# AU_MacroPad.net
KiCad netlist of a schematic drawn in EAGLE
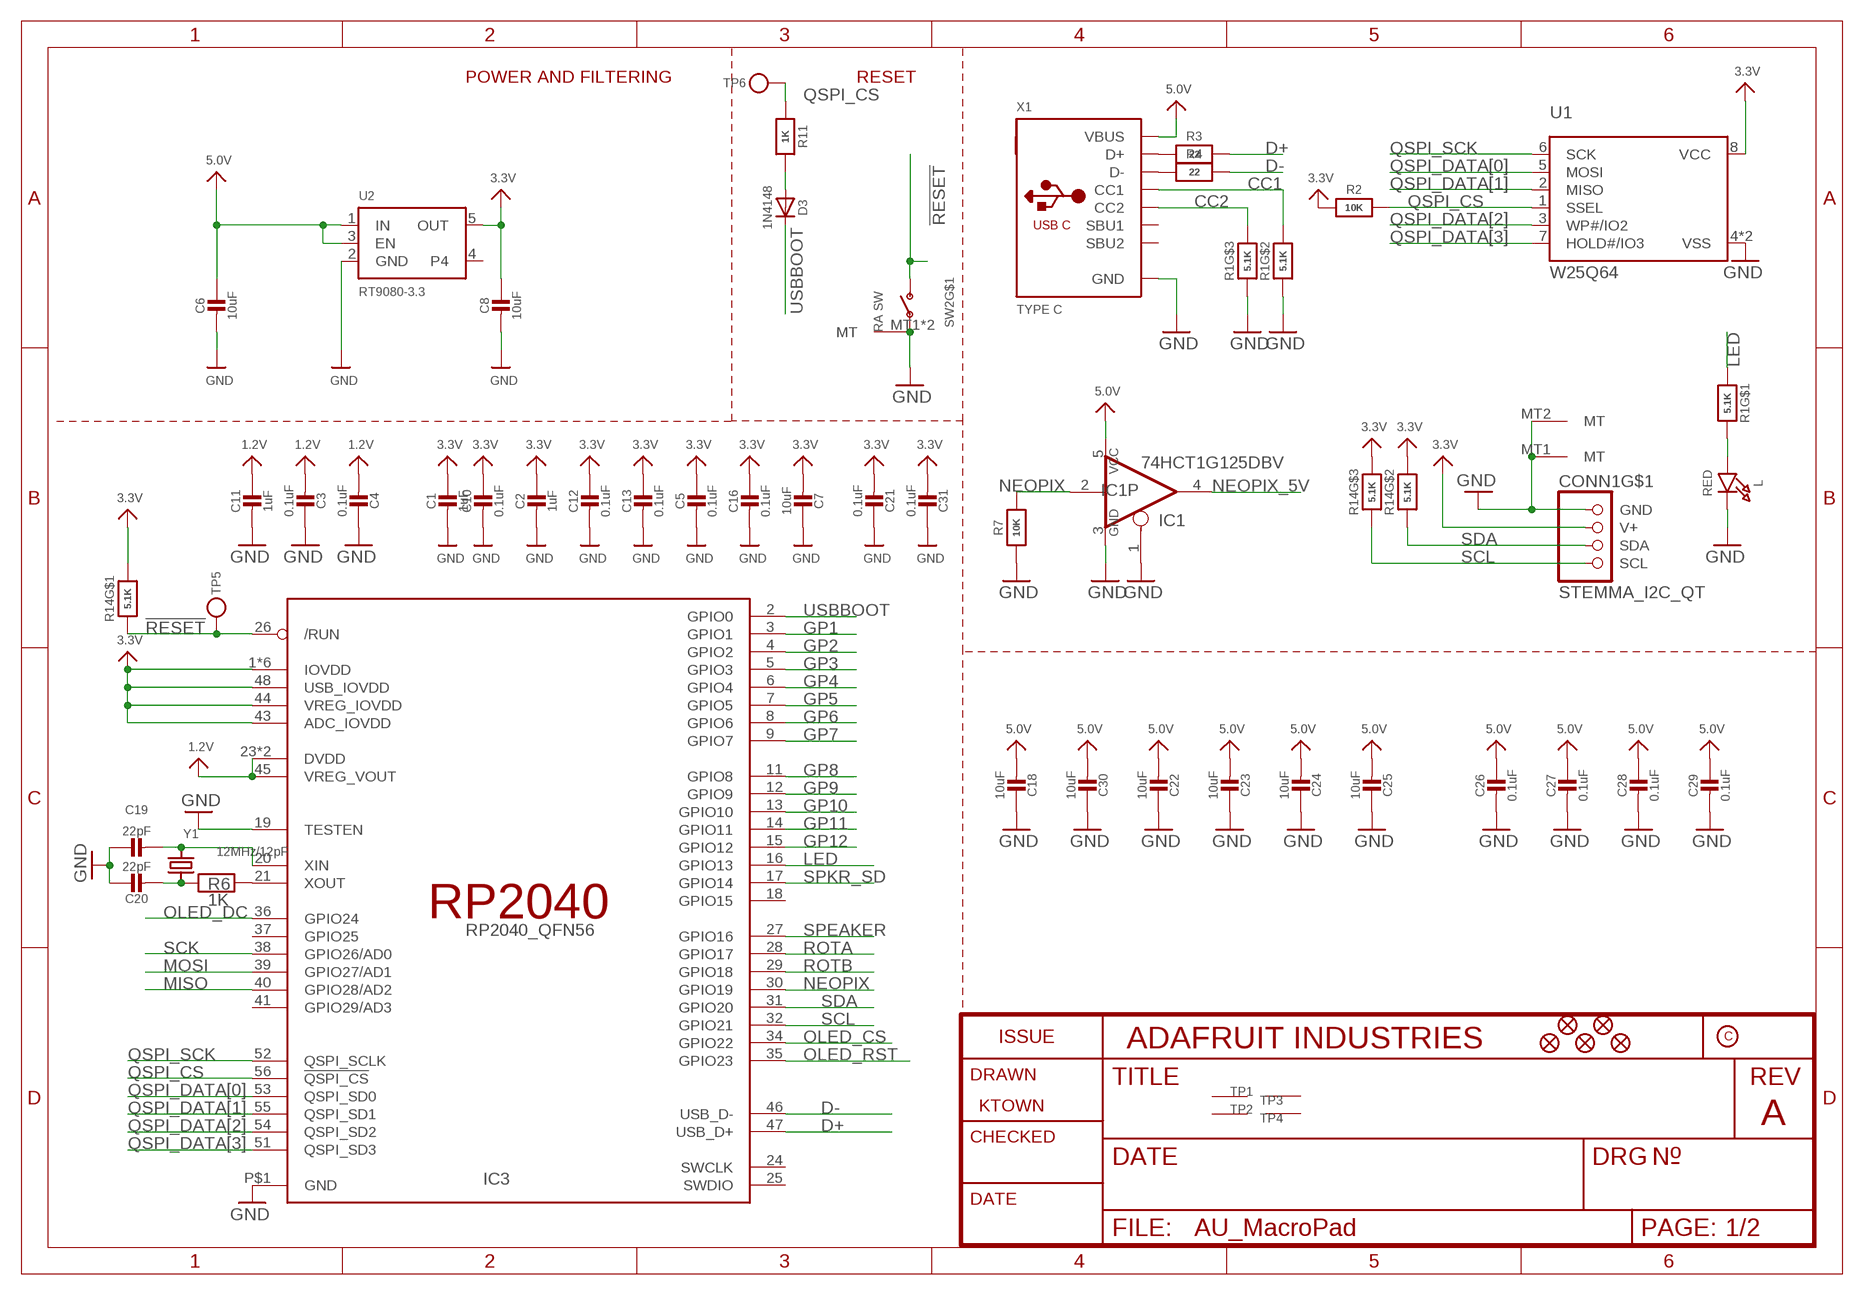
[diagram p0: schematic, sheet 1]
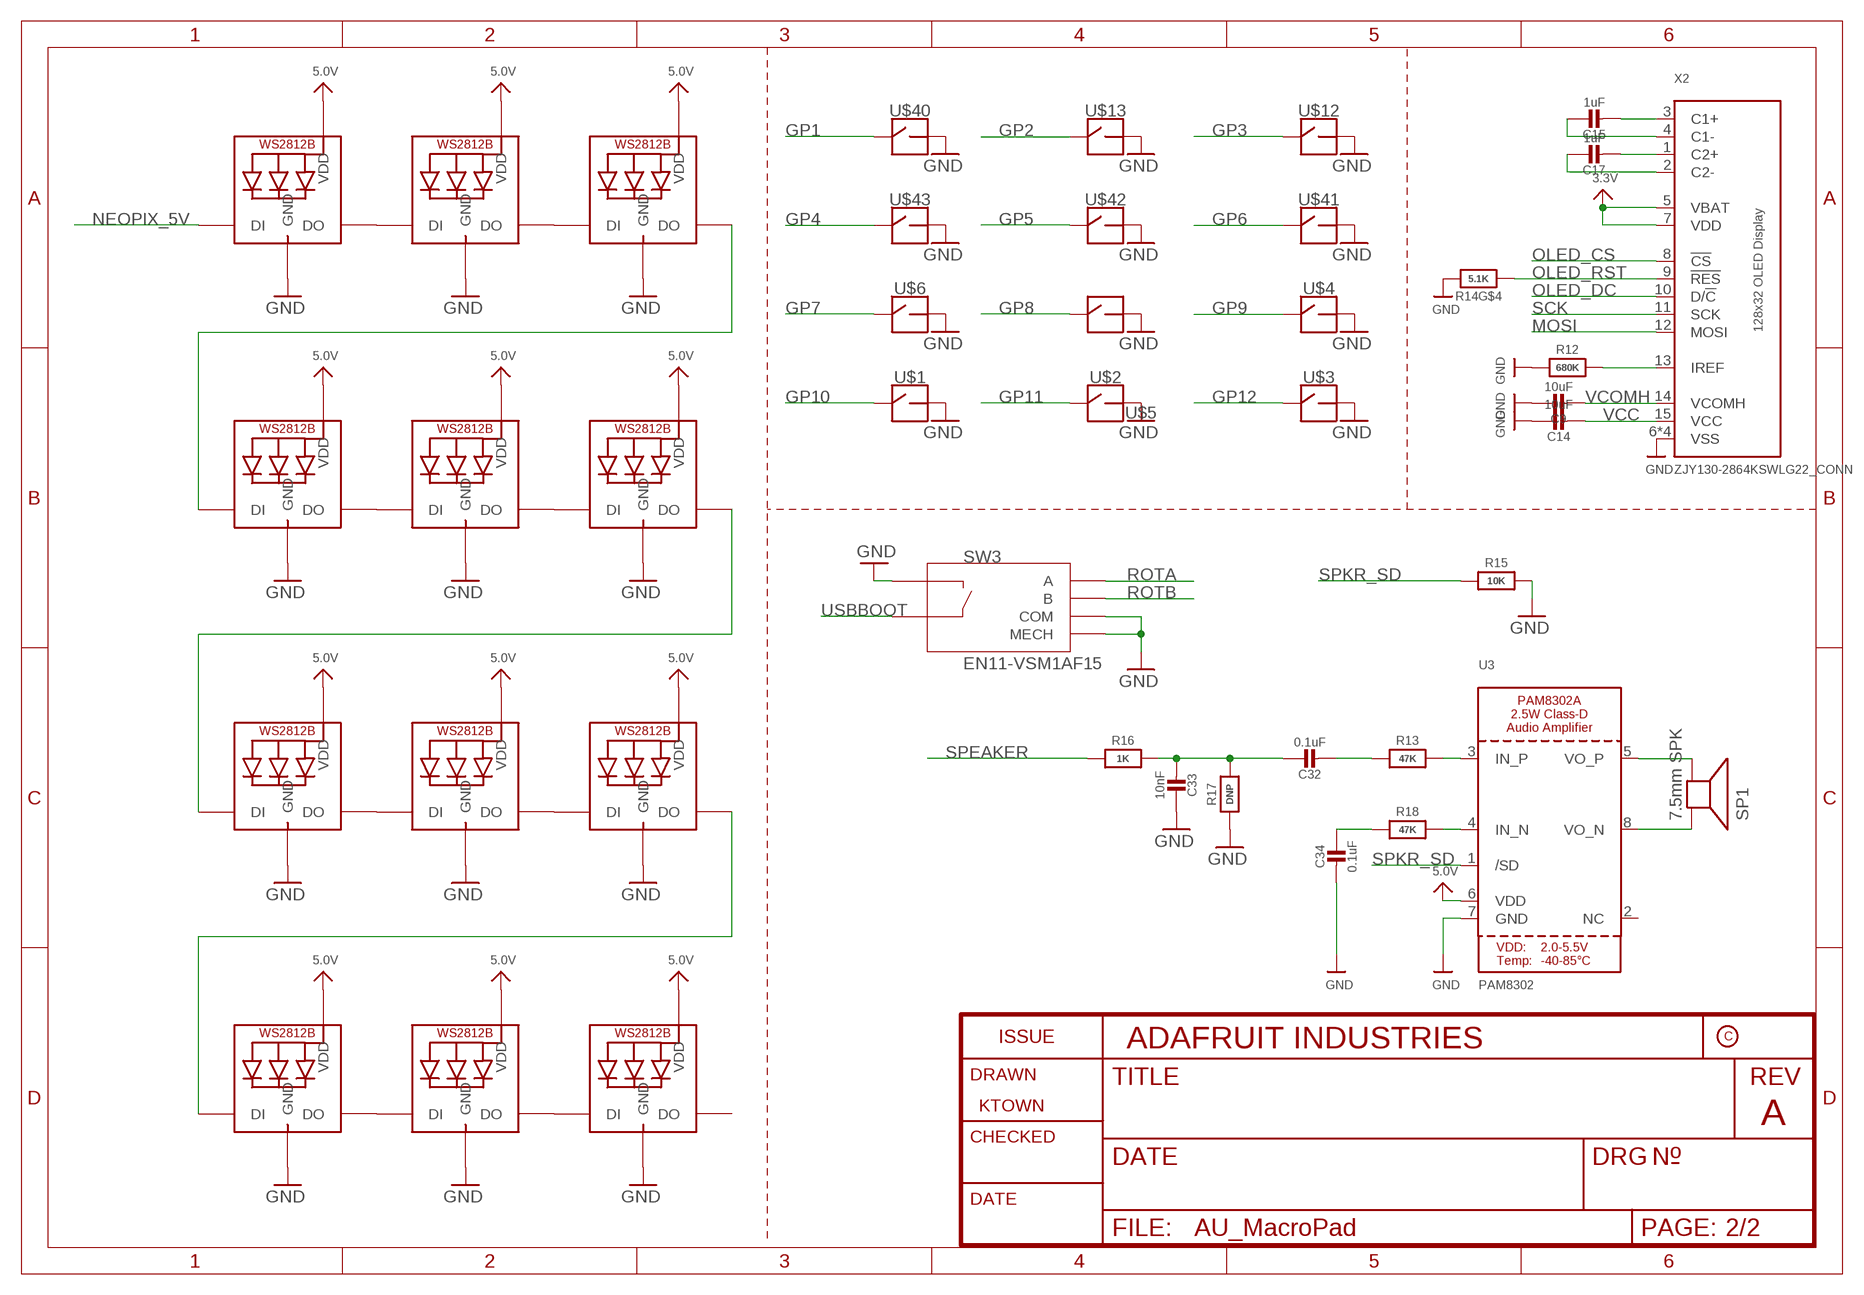
[diagram p1: schematic, sheet 2]

(export (version "E")
  (design (tool "Eeschema 10.0.6"))
  (components
    (comp (ref "C9")
      (value "10uF")
      (footprint "eagle-import:0805-NO")
      (libsource (lib "eagle-import") (part "CAP_CERAMIC0805-NOOUTLINE"))
    )
    (comp (ref "C14")
      (value "10uF")
      (footprint "eagle-import:0805-NO")
      (libsource (lib "eagle-import") (part "CAP_CERAMIC0805-NOOUTLINE"))
    )
    (comp (ref "C15")
      (value "1uF")
      (footprint "eagle-import:0603-NO")
      (libsource (lib "eagle-import") (part "CAP_CERAMIC0603_NO"))
    )
    (comp (ref "C17")
      (value "1uF")
      (footprint "eagle-import:0603-NO")
      (libsource (lib "eagle-import") (part "CAP_CERAMIC0603_NO"))
    )
    (comp (ref "C32")
      (value "0.1uF")
      (footprint "eagle-import:0603-NO")
      (libsource (lib "eagle-import") (part "CAP_CERAMIC0603_NO"))
    )
    (comp (ref "C33")
      (value "10nF")
      (footprint "eagle-import:0603-NO")
      (libsource (lib "eagle-import") (part "CAP_CERAMIC0603_NO"))
    )
    (comp (ref "C34")
      (value "0.1uF")
      (footprint "eagle-import:0603-NO")
      (libsource (lib "eagle-import") (part "CAP_CERAMIC0603_NO"))
    )
    (comp (ref "LED1")
      (value "WS2812B_SK6812E")
      (footprint "eagle-import:NEO3535_REVERSE")
      (libsource (lib "eagle-import") (part "WS2812B_SK6812E"))
    )
    (comp (ref "LED2")
      (value "WS2812B_SK6812E")
      (footprint "eagle-import:NEO3535_REVERSE")
      (libsource (lib "eagle-import") (part "WS2812B_SK6812E"))
    )
    (comp (ref "LED3")
      (value "WS2812B_SK6812E")
      (footprint "eagle-import:NEO3535_REVERSE")
      (libsource (lib "eagle-import") (part "WS2812B_SK6812E"))
    )
    (comp (ref "LED4")
      (value "WS2812B_SK6812E")
      (footprint "eagle-import:NEO3535_REVERSE")
      (libsource (lib "eagle-import") (part "WS2812B_SK6812E"))
    )
    (comp (ref "LED5")
      (value "WS2812B_SK6812E")
      (footprint "eagle-import:NEO3535_REVERSE")
      (libsource (lib "eagle-import") (part "WS2812B_SK6812E"))
    )
    (comp (ref "LED6")
      (value "WS2812B_SK6812E")
      (footprint "eagle-import:NEO3535_REVERSE")
      (libsource (lib "eagle-import") (part "WS2812B_SK6812E"))
    )
    (comp (ref "LED7")
      (value "WS2812B_SK6812E")
      (footprint "eagle-import:NEO3535_REVERSE")
      (libsource (lib "eagle-import") (part "WS2812B_SK6812E"))
    )
    (comp (ref "LED8")
      (value "WS2812B_SK6812E")
      (footprint "eagle-import:NEO3535_REVERSE")
      (libsource (lib "eagle-import") (part "WS2812B_SK6812E"))
    )
    (comp (ref "LED9")
      (value "WS2812B_SK6812E")
      (footprint "eagle-import:NEO3535_REVERSE")
      (libsource (lib "eagle-import") (part "WS2812B_SK6812E"))
    )
    (comp (ref "LED10")
      (value "WS2812B_SK6812E")
      (footprint "eagle-import:NEO3535_REVERSE")
      (libsource (lib "eagle-import") (part "WS2812B_SK6812E"))
    )
    (comp (ref "LED11")
      (value "WS2812B_SK6812E")
      (footprint "eagle-import:NEO3535_REVERSE")
      (libsource (lib "eagle-import") (part "WS2812B_SK6812E"))
    )
    (comp (ref "LED12")
      (value "WS2812B_SK6812E")
      (footprint "eagle-import:NEO3535_REVERSE")
      (libsource (lib "eagle-import") (part "WS2812B_SK6812E"))
    )
    (comp (ref "R12")
      (value "680K")
      (footprint "eagle-import:0603-NO")
      (libsource (lib "eagle-import") (part "RESISTOR_0603_NOOUT"))
    )
    (comp (ref "R13")
      (value "47K")
      (footprint "eagle-import:0603-NO")
      (libsource (lib "eagle-import") (part "RESISTOR_0603_NOOUT"))
    )
    (comp (ref "R14")
      (value "5.1K")
      (footprint "eagle-import:RESPACK_4X0603")
      (libsource (lib "eagle-import") (part "RESISTOR_4PACK"))
    )
    (comp (ref "R15")
      (value "10K")
      (footprint "eagle-import:0603-NO")
      (libsource (lib "eagle-import") (part "RESISTOR_0603_NOOUT"))
    )
    (comp (ref "R16")
      (value "1K")
      (footprint "eagle-import:0603-NO")
      (libsource (lib "eagle-import") (part "RESISTOR_0603_NOOUT"))
    )
    (comp (ref "R17")
      (value "DNP")
      (footprint "eagle-import:0603-NO")
      (libsource (lib "eagle-import") (part "RESISTOR_0603_NOOUT"))
    )
    (comp (ref "R18")
      (value "47K")
      (footprint "eagle-import:0603-NO")
      (libsource (lib "eagle-import") (part "RESISTOR_0603_NOOUT"))
    )
    (comp (ref "SP1")
      (value "7.5mm SPK")
      (footprint "eagle-import:BUZZER_SMT_7.5MM")
      (fields (field (name "ROT") "0"))
      (libsource (lib "eagle-import") (part "SPEAKER_7.5MM"))
    )
    (comp (ref "SW3")
      (value "EN11-VSM1AF15")
      (footprint "eagle-import:EN11-VSM1AF15")
      (libsource (lib "eagle-import") (part "EN11-VSM1AF15"))
    )
    (comp (ref "U$1")
      (value "SOCKET")
      (footprint "eagle-import:KAILH_SOCKET")
      (fields (field (name "XOFFSET") "-0.75"))
      (libsource (lib "eagle-import") (part "KBD_SWITCH_KAILH_SOCKETBOX_JADE_KAILH_SOCKET"))
    )
    (comp (ref "U$2")
      (value "SOCKET")
      (footprint "eagle-import:KAILH_SOCKET")
      (fields (field (name "XOFFSET") "-0.75"))
      (libsource (lib "eagle-import") (part "KBD_SWITCH_KAILH_SOCKETBOX_JADE_KAILH_SOCKET"))
    )
    (comp (ref "U$3")
      (value "SOCKET")
      (footprint "eagle-import:KAILH_SOCKET")
      (fields (field (name "XOFFSET") "-0.75"))
      (libsource (lib "eagle-import") (part "KBD_SWITCH_KAILH_SOCKETBOX_JADE_KAILH_SOCKET"))
    )
    (comp (ref "U$4")
      (value "SOCKET")
      (footprint "eagle-import:KAILH_SOCKET")
      (fields (field (name "XOFFSET") "-0.75"))
      (libsource (lib "eagle-import") (part "KBD_SWITCH_KAILH_SOCKETBOX_JADE_KAILH_SOCKET"))
    )
    (comp (ref "U$5")
      (value "SOCKET")
      (footprint "eagle-import:KAILH_SOCKET")
      (fields (field (name "XOFFSET") "-0.75"))
      (libsource (lib "eagle-import") (part "KBD_SWITCH_KAILH_SOCKETBOX_JADE_KAILH_SOCKET"))
    )
    (comp (ref "U$6")
      (value "SOCKET")
      (footprint "eagle-import:KAILH_SOCKET")
      (fields (field (name "XOFFSET") "-0.75"))
      (libsource (lib "eagle-import") (part "KBD_SWITCH_KAILH_SOCKETBOX_JADE_KAILH_SOCKET"))
    )
    (comp (ref "U$12")
      (value "SOCKET")
      (footprint "eagle-import:KAILH_SOCKET")
      (fields (field (name "XOFFSET") "-0.75"))
      (libsource (lib "eagle-import") (part "KBD_SWITCH_KAILH_SOCKETBOX_JADE_KAILH_SOCKET"))
    )
    (comp (ref "U$13")
      (value "SOCKET")
      (footprint "eagle-import:KAILH_SOCKET")
      (fields (field (name "XOFFSET") "-0.75"))
      (libsource (lib "eagle-import") (part "KBD_SWITCH_KAILH_SOCKETBOX_JADE_KAILH_SOCKET"))
    )
    (comp (ref "U$40")
      (value "SOCKET")
      (footprint "eagle-import:KAILH_SOCKET")
      (fields (field (name "XOFFSET") "-0.75"))
      (libsource (lib "eagle-import") (part "KBD_SWITCH_KAILH_SOCKETBOX_JADE_KAILH_SOCKET"))
    )
    (comp (ref "U$41")
      (value "SOCKET")
      (footprint "eagle-import:KAILH_SOCKET")
      (fields (field (name "XOFFSET") "-0.75"))
      (libsource (lib "eagle-import") (part "KBD_SWITCH_KAILH_SOCKETBOX_JADE_KAILH_SOCKET"))
    )
    (comp (ref "U$42")
      (value "SOCKET")
      (footprint "eagle-import:KAILH_SOCKET")
      (fields (field (name "XOFFSET") "-0.75"))
      (libsource (lib "eagle-import") (part "KBD_SWITCH_KAILH_SOCKETBOX_JADE_KAILH_SOCKET"))
    )
    (comp (ref "U$43")
      (value "SOCKET")
      (footprint "eagle-import:KAILH_SOCKET")
      (fields (field (name "XOFFSET") "-0.75"))
      (libsource (lib "eagle-import") (part "KBD_SWITCH_KAILH_SOCKETBOX_JADE_KAILH_SOCKET"))
    )
    (comp (ref "U3")
      (value "PAM8302")
      (footprint "eagle-import:MSOP8_0.65MM")
      (libsource (lib "eagle-import") (part "AUDIOAMP_PAM8302A"))
    )
    (comp (ref "X2")
      (value "ZJY130-2864KSWLG22_CONN")
      (footprint "eagle-import:ZJY130-2864KSWLG22_JUSTCONN")
      (libsource (lib "eagle-import") (part "ZJY130-2864KSWLG22_CONN"))
    )
    (comp (ref "C1")
      (value "1uF")
      (footprint "eagle-import:0603-NO")
      (libsource (lib "eagle-import") (part "CAP_CERAMIC0603_NO"))
    )
    (comp (ref "C2")
      (value "1uF")
      (footprint "eagle-import:0603-NO")
      (libsource (lib "eagle-import") (part "CAP_CERAMIC0603_NO"))
    )
    (comp (ref "C3")
      (value "0.1uF")
      (footprint "eagle-import:0603-NO")
      (libsource (lib "eagle-import") (part "CAP_CERAMIC0603_NO"))
    )
    (comp (ref "C4")
      (value "0.1uF")
      (footprint "eagle-import:0603-NO")
      (libsource (lib "eagle-import") (part "CAP_CERAMIC0603_NO"))
    )
    (comp (ref "C5")
      (value "0.1uF")
      (footprint "eagle-import:0603-NO")
      (libsource (lib "eagle-import") (part "CAP_CERAMIC0603_NO"))
    )
    (comp (ref "C6")
      (value "10uF")
      (footprint "eagle-import:0805-NO")
      (libsource (lib "eagle-import") (part "CAP_CERAMIC0805-NOOUTLINE"))
    )
    (comp (ref "C7")
      (value "10uF")
      (footprint "eagle-import:0805-NO")
      (libsource (lib "eagle-import") (part "CAP_CERAMIC0805-NOOUTLINE"))
    )
    (comp (ref "C8")
      (value "10uF")
      (footprint "eagle-import:0805-NO")
      (fields (field (name "REV") "D"))
      (libsource (lib "eagle-import") (part "CAP_CERAMIC0805-NOOUTLINE"))
    )
    (comp (ref "C10")
      (value "0.1uF")
      (footprint "eagle-import:0603-NO")
      (libsource (lib "eagle-import") (part "CAP_CERAMIC0603_NO"))
    )
    (comp (ref "C11")
      (value "1uF")
      (footprint "eagle-import:0603-NO")
      (libsource (lib "eagle-import") (part "CAP_CERAMIC0603_NO"))
    )
    (comp (ref "C12")
      (value "0.1uF")
      (footprint "eagle-import:0603-NO")
      (libsource (lib "eagle-import") (part "CAP_CERAMIC0603_NO"))
    )
    (comp (ref "C13")
      (value "0.1uF")
      (footprint "eagle-import:0603-NO")
      (libsource (lib "eagle-import") (part "CAP_CERAMIC0603_NO"))
    )
    (comp (ref "C16")
      (value "0.1uF")
      (footprint "eagle-import:0603-NO")
      (libsource (lib "eagle-import") (part "CAP_CERAMIC0603_NO"))
    )
    (comp (ref "C18")
      (value "10uF")
      (footprint "eagle-import:0805-NO")
      (libsource (lib "eagle-import") (part "CAP_CERAMIC0805-NOOUTLINE"))
    )
    (comp (ref "C19")
      (value "22pF")
      (footprint "eagle-import:0603-NO")
      (libsource (lib "eagle-import") (part "CAP_CERAMIC0603_NO"))
    )
    (comp (ref "C20")
      (value "22pF")
      (footprint "eagle-import:0603-NO")
      (libsource (lib "eagle-import") (part "CAP_CERAMIC0603_NO"))
    )
    (comp (ref "C21")
      (value "0.1uF")
      (footprint "eagle-import:0603-NO")
      (libsource (lib "eagle-import") (part "CAP_CERAMIC0603_NO"))
    )
    (comp (ref "C22")
      (value "10uF")
      (footprint "eagle-import:0805-NO")
      (libsource (lib "eagle-import") (part "CAP_CERAMIC0805-NOOUTLINE"))
    )
    (comp (ref "C23")
      (value "10uF")
      (footprint "eagle-import:0805-NO")
      (libsource (lib "eagle-import") (part "CAP_CERAMIC0805-NOOUTLINE"))
    )
    (comp (ref "C24")
      (value "10uF")
      (footprint "eagle-import:0805-NO")
      (libsource (lib "eagle-import") (part "CAP_CERAMIC0805-NOOUTLINE"))
    )
    (comp (ref "C25")
      (value "10uF")
      (footprint "eagle-import:0805-NO")
      (libsource (lib "eagle-import") (part "CAP_CERAMIC0805-NOOUTLINE"))
    )
    (comp (ref "C26")
      (value "0.1uF")
      (footprint "eagle-import:0603-NO")
      (libsource (lib "eagle-import") (part "CAP_CERAMIC0603_NO"))
    )
    (comp (ref "C27")
      (value "0.1uF")
      (footprint "eagle-import:0603-NO")
      (libsource (lib "eagle-import") (part "CAP_CERAMIC0603_NO"))
    )
    (comp (ref "C28")
      (value "0.1uF")
      (footprint "eagle-import:0603-NO")
      (libsource (lib "eagle-import") (part "CAP_CERAMIC0603_NO"))
    )
    (comp (ref "C29")
      (value "0.1uF")
      (footprint "eagle-import:0603-NO")
      (libsource (lib "eagle-import") (part "CAP_CERAMIC0603_NO"))
    )
    (comp (ref "C30")
      (value "10uF")
      (footprint "eagle-import:0805-NO")
      (libsource (lib "eagle-import") (part "CAP_CERAMIC0805-NOOUTLINE"))
    )
    (comp (ref "C31")
      (value "0.1uF")
      (footprint "eagle-import:0603-NO")
      (libsource (lib "eagle-import") (part "CAP_CERAMIC0603_NO"))
    )
    (comp (ref "CONN1")
      (value "STEMMA_I2C_QT")
      (footprint "eagle-import:JST_SH4")
      (libsource (lib "eagle-import") (part "STEMMA_I2C_QT"))
    )
    (comp (ref "D3")
      (value "1N4148")
      (footprint "eagle-import:SOD-323")
      (libsource (lib "eagle-import") (part "DIODESOD-323"))
    )
    (comp (ref "IC1")
      (value "74HCT1G125DBV")
      (footprint "eagle-import:SOT23-5")
      (libsource (lib "eagle-import") (part "741G125DBVAHC"))
    )
    (comp (ref "IC3")
      (value "RP2040_QFN56")
      (footprint "eagle-import:QFN56_7MM_REDUCEDEPAD")
      (libsource (lib "eagle-import") (part "RP2040_QFN56"))
    )
    (comp (ref "L")
      (value "RED")
      (footprint "eagle-import:CHIPLED_0603_NOOUTLINE")
      (libsource (lib "eagle-import") (part "LED0603_NOOUTLINE"))
    )
    (comp (ref "R1")
      (value "5.1K")
      (footprint "eagle-import:RESPACK_4X0603")
      (libsource (lib "eagle-import") (part "RESISTOR_4PACK"))
    )
    (comp (ref "R2")
      (value "10K")
      (footprint "eagle-import:0603-NO")
      (libsource (lib "eagle-import") (part "RESISTOR_0603_NOOUT"))
    )
    (comp (ref "R3")
      (value "22")
      (footprint "eagle-import:0603-NO")
      (libsource (lib "eagle-import") (part "RESISTOR_0603_NOOUT"))
    )
    (comp (ref "R4")
      (value "22")
      (footprint "eagle-import:0603-NO")
      (libsource (lib "eagle-import") (part "RESISTOR_0603_NOOUT"))
    )
    (comp (ref "R6")
      (value "1K")
      (footprint "eagle-import:0603-NO")
      (libsource (lib "eagle-import") (part "RESISTOR_0603_NOOUT"))
    )
    (comp (ref "R7")
      (value "10K")
      (footprint "eagle-import:0603-NO")
      (libsource (lib "eagle-import") (part "RESISTOR_0603_NOOUT"))
    )
    (comp (ref "R11")
      (value "1K")
      (footprint "eagle-import:0603-NO")
      (libsource (lib "eagle-import") (part "RESISTOR_0603_NOOUT"))
    )
    (comp (ref "SW2")
      (value "RA SW")
      (footprint "eagle-import:SPST_TACTILE_RA")
      (libsource (lib "eagle-import") (part "SWITCH_SPST_MNT_TACT_RA"))
    )
    (comp (ref "TP1")
      (value "SEWTAP_SMTNUTM3")
      (footprint "eagle-import:SMT_NUT_3MM")
      (libsource (lib "eagle-import") (part "SEWTAP_SMTNUTM3"))
    )
    (comp (ref "TP2")
      (value "SEWTAP_SMTNUTM3")
      (footprint "eagle-import:SMT_NUT_3MM")
      (libsource (lib "eagle-import") (part "SEWTAP_SMTNUTM3"))
    )
    (comp (ref "TP3")
      (value "SEWTAP_SMTNUTM3")
      (footprint "eagle-import:SMT_NUT_3MM")
      (libsource (lib "eagle-import") (part "SEWTAP_SMTNUTM3"))
    )
    (comp (ref "TP4")
      (value "SEWTAP_SMTNUTM3")
      (footprint "eagle-import:SMT_NUT_3MM")
      (libsource (lib "eagle-import") (part "SEWTAP_SMTNUTM3"))
    )
    (comp (ref "TP5")
      (value "TESTPOINTROUND1.5MMNO")
      (footprint "eagle-import:TESTPOINT_ROUND_1.5MM_NO")
      (libsource (lib "eagle-import") (part "TESTPOINTROUND1.5MMNO"))
    )
    (comp (ref "TP6")
      (value "TESTPOINTROUND1.5MMNO")
      (footprint "eagle-import:TESTPOINT_ROUND_1.5MM_NO")
      (libsource (lib "eagle-import") (part "TESTPOINTROUND1.5MMNO"))
    )
    (comp (ref "U$34")
      (value "FIDUCIAL_1MM")
      (footprint "eagle-import:FIDUCIAL_1MM")
      (libsource (lib "eagle-import") (part "FIDUCIAL_1MM"))
    )
    (comp (ref "U$35")
      (value "FIDUCIAL_1MM")
      (footprint "eagle-import:FIDUCIAL_1MM")
      (libsource (lib "eagle-import") (part "FIDUCIAL_1MM"))
    )
    (comp (ref "U$79")
      (value "FIDUCIAL_1MM")
      (footprint "eagle-import:FIDUCIAL_1MM")
      (libsource (lib "eagle-import") (part "FIDUCIAL_1MM"))
    )
    (comp (ref "U$80")
      (value "FIDUCIAL_1MM")
      (footprint "eagle-import:FIDUCIAL_1MM")
      (libsource (lib "eagle-import") (part "FIDUCIAL_1MM"))
    )
    (comp (ref "U$83")
      (value "FIDUCIAL_1MM")
      (footprint "eagle-import:FIDUCIAL_1MM")
      (libsource (lib "eagle-import") (part "FIDUCIAL_1MM"))
    )
    (comp (ref "U1")
      (value "W25Q64")
      (footprint "eagle-import:USON8_4X4")
      (libsource (lib "eagle-import") (part "SPIFLASH_8PIN_4X4"))
    )
    (comp (ref "U2")
      (value "RT9080-3.3")
      (footprint "eagle-import:SOT23-5")
      (fields (field (name "JLC_ROTATION") "0"))
      (libsource (lib "eagle-import") (part "VREG_SOT23-5"))
    )
    (comp (ref "X1")
      (value "TYPE C")
      (footprint "eagle-import:USB_C_CUSB31-CFM2AX-01-X")
      (libsource (lib "eagle-import") (part "USB_C"))
    )
    (comp (ref "Y1")
      (value "12MHz/12pF")
      (footprint "eagle-import:CRYSTAL_2.5X2")
      (libsource (lib "eagle-import") (part "CRYSTAL2.5X2.0"))
    )
  )
  (nets
    (net (code "1") (name "1.2V") (class "Default")
      (node (ref "C11") (pin "1") (pinfunction "1_1") (pintype "passive"))
      (node (ref "C3") (pin "2") (pinfunction "2_2") (pintype "passive"))
      (node (ref "C4") (pin "2") (pinfunction "2_2") (pintype "passive"))
      (node (ref "IC3") (pin "23") (pinfunction "DVDD_23") (pintype "power_in"))
      (node (ref "IC3") (pin "45") (pinfunction "VREG_VOUT_45") (pintype "power_in"))
      (node (ref "IC3") (pin "50") (pinfunction "DVDD_50") (pintype "power_in"))
    )
    (net (code "2") (name "3.3V") (class "Default")
      (node (ref "C1") (pin "1") (pinfunction "1_1") (pintype "passive"))
      (node (ref "C10") (pin "1") (pinfunction "1_1") (pintype "passive"))
      (node (ref "C12") (pin "1") (pinfunction "1_1") (pintype "passive"))
      (node (ref "C13") (pin "1") (pinfunction "1_1") (pintype "passive"))
      (node (ref "C16") (pin "1") (pinfunction "1_1") (pintype "passive"))
      (node (ref "C2") (pin "1") (pinfunction "1_1") (pintype "passive"))
      (node (ref "C21") (pin "2") (pinfunction "2_2") (pintype "passive"))
      (node (ref "C31") (pin "2") (pinfunction "2_2") (pintype "passive"))
      (node (ref "C5") (pin "1") (pinfunction "1_1") (pintype "passive"))
      (node (ref "C7") (pin "2") (pinfunction "2_2") (pintype "passive"))
      (node (ref "C8") (pin "1") (pinfunction "1_1") (pintype "passive"))
      (node (ref "CONN1") (pin "2") (pinfunction "V+_2") (pintype "passive"))
      (node (ref "IC3") (pin "1") (pinfunction "IOVDD_1") (pintype "power_in"))
      (node (ref "IC3") (pin "10") (pinfunction "IOVDD_10") (pintype "power_in"))
      (node (ref "IC3") (pin "22") (pinfunction "IOVDD_22") (pintype "power_in"))
      (node (ref "IC3") (pin "33") (pinfunction "IOVDD_33") (pintype "power_in"))
      (node (ref "IC3") (pin "42") (pinfunction "IOVDD_42") (pintype "power_in"))
      (node (ref "IC3") (pin "43") (pinfunction "ADC_IOVDD_43") (pintype "power_in"))
      (node (ref "IC3") (pin "44") (pinfunction "VREG_IOVDD_44") (pintype "power_in"))
      (node (ref "IC3") (pin "48") (pinfunction "USB_IOVDD_48") (pintype "power_in"))
      (node (ref "IC3") (pin "49") (pinfunction "IOVDD_49") (pintype "power_in"))
      (node (ref "R14") (pin "6") (pinfunction "2_6") (pintype "passive"))
      (node (ref "R14") (pin "7") (pinfunction "2_7") (pintype "passive"))
      (node (ref "R14") (pin "8") (pinfunction "2_8") (pintype "passive"))
      (node (ref "R2") (pin "1") (pinfunction "1_1") (pintype "passive"))
      (node (ref "U1") (pin "8") (pinfunction "VCC_8") (pintype "bidirectional"))
      (node (ref "U2") (pin "5") (pinfunction "OUT_5") (pintype "power_in"))
      (node (ref "X2") (pin "5") (pinfunction "VBAT_5") (pintype "power_in"))
      (node (ref "X2") (pin "7") (pinfunction "VDD_7") (pintype "power_in"))
    )
    (net (code "3") (name "5.0V") (class "Default")
      (node (ref "C18") (pin "2") (pinfunction "2_2") (pintype "passive"))
      (node (ref "C22") (pin "2") (pinfunction "2_2") (pintype "passive"))
      (node (ref "C23") (pin "2") (pinfunction "2_2") (pintype "passive"))
      (node (ref "C24") (pin "2") (pinfunction "2_2") (pintype "passive"))
      (node (ref "C25") (pin "2") (pinfunction "2_2") (pintype "passive"))
      (node (ref "C26") (pin "1") (pinfunction "1_1") (pintype "passive"))
      (node (ref "C27") (pin "1") (pinfunction "1_1") (pintype "passive"))
      (node (ref "C28") (pin "1") (pinfunction "1_1") (pintype "passive"))
      (node (ref "C29") (pin "1") (pinfunction "1_1") (pintype "passive"))
      (node (ref "C30") (pin "2") (pinfunction "2_2") (pintype "passive"))
      (node (ref "C6") (pin "1") (pinfunction "1_1") (pintype "passive"))
      (node (ref "IC1") (pin "5") (pinfunction "VCC_5") (pintype "power_in"))
      (node (ref "LED1") (pin "1-VDD") (pinfunction "VDD_1-VDD") (pintype "power_in"))
      (node (ref "LED10") (pin "1-VDD") (pinfunction "VDD_1-VDD") (pintype "power_in"))
      (node (ref "LED11") (pin "1-VDD") (pinfunction "VDD_1-VDD") (pintype "power_in"))
      (node (ref "LED12") (pin "1-VDD") (pinfunction "VDD_1-VDD") (pintype "power_in"))
      (node (ref "LED2") (pin "1-VDD") (pinfunction "VDD_1-VDD") (pintype "power_in"))
      (node (ref "LED3") (pin "1-VDD") (pinfunction "VDD_1-VDD") (pintype "power_in"))
      (node (ref "LED4") (pin "1-VDD") (pinfunction "VDD_1-VDD") (pintype "power_in"))
      (node (ref "LED5") (pin "1-VDD") (pinfunction "VDD_1-VDD") (pintype "power_in"))
      (node (ref "LED6") (pin "1-VDD") (pinfunction "VDD_1-VDD") (pintype "power_in"))
      (node (ref "LED7") (pin "1-VDD") (pinfunction "VDD_1-VDD") (pintype "power_in"))
      (node (ref "LED8") (pin "1-VDD") (pinfunction "VDD_1-VDD") (pintype "power_in"))
      (node (ref "LED9") (pin "1-VDD") (pinfunction "VDD_1-VDD") (pintype "power_in"))
      (node (ref "U2") (pin "1") (pinfunction "IN_1") (pintype "power_in"))
      (node (ref "U2") (pin "3") (pinfunction "EN_3") (pintype "input"))
      (node (ref "U3") (pin "6") (pinfunction "VDD_6") (pintype "power_in"))
      (node (ref "X1") (pin "A4B9") (pinfunction "VBUS_A4B9") (pintype "power_in"))
      (node (ref "X1") (pin "B4A9") (pinfunction "VBUS_B4A9") (pintype "power_in"))
    )
    (net (code "4") (name "CC1") (class "Default")
      (node (ref "R1") (pin "7") (pinfunction "2_7") (pintype "passive"))
      (node (ref "X1") (pin "A5") (pinfunction "CC1_A5") (pintype "bidirectional"))
    )
    (net (code "5") (name "CC2") (class "Default")
      (node (ref "R1") (pin "6") (pinfunction "2_6") (pintype "passive"))
      (node (ref "X1") (pin "B5") (pinfunction "CC2_B5") (pintype "bidirectional"))
    )
    (net (code "6") (name "D+") (class "Default")
      (node (ref "IC3") (pin "47") (pinfunction "USB_D+_47") (pintype "bidirectional"))
      (node (ref "R3") (pin "2") (pinfunction "2_2") (pintype "passive"))
    )
    (net (code "7") (name "D-") (class "Default")
      (node (ref "IC3") (pin "46") (pinfunction "USB_D-_46") (pintype "bidirectional"))
      (node (ref "R4") (pin "2") (pinfunction "2_2") (pintype "passive"))
    )
    (net (code "8") (name "GND") (class "Default")
      (node (ref "C1") (pin "2") (pinfunction "2_2") (pintype "passive"))
      (node (ref "C10") (pin "2") (pinfunction "2_2") (pintype "passive"))
      (node (ref "C11") (pin "2") (pinfunction "2_2") (pintype "passive"))
      (node (ref "C12") (pin "2") (pinfunction "2_2") (pintype "passive"))
      (node (ref "C13") (pin "2") (pinfunction "2_2") (pintype "passive"))
      (node (ref "C14") (pin "1") (pinfunction "1_1") (pintype "passive"))
      (node (ref "C16") (pin "2") (pinfunction "2_2") (pintype "passive"))
      (node (ref "C18") (pin "1") (pinfunction "1_1") (pintype "passive"))
      (node (ref "C19") (pin "1") (pinfunction "1_1") (pintype "passive"))
      (node (ref "C2") (pin "2") (pinfunction "2_2") (pintype "passive"))
      (node (ref "C20") (pin "1") (pinfunction "1_1") (pintype "passive"))
      (node (ref "C21") (pin "1") (pinfunction "1_1") (pintype "passive"))
      (node (ref "C22") (pin "1") (pinfunction "1_1") (pintype "passive"))
      (node (ref "C23") (pin "1") (pinfunction "1_1") (pintype "passive"))
      (node (ref "C24") (pin "1") (pinfunction "1_1") (pintype "passive"))
      (node (ref "C25") (pin "1") (pinfunction "1_1") (pintype "passive"))
      (node (ref "C26") (pin "2") (pinfunction "2_2") (pintype "passive"))
      (node (ref "C27") (pin "2") (pinfunction "2_2") (pintype "passive"))
      (node (ref "C28") (pin "2") (pinfunction "2_2") (pintype "passive"))
      (node (ref "C29") (pin "2") (pinfunction "2_2") (pintype "passive"))
      (node (ref "C3") (pin "1") (pinfunction "1_1") (pintype "passive"))
      (node (ref "C30") (pin "1") (pinfunction "1_1") (pintype "passive"))
      (node (ref "C31") (pin "1") (pinfunction "1_1") (pintype "passive"))
      (node (ref "C33") (pin "1") (pinfunction "1_1") (pintype "passive"))
      (node (ref "C34") (pin "2") (pinfunction "2_2") (pintype "passive"))
      (node (ref "C4") (pin "1") (pinfunction "1_1") (pintype "passive"))
      (node (ref "C5") (pin "2") (pinfunction "2_2") (pintype "passive"))
      (node (ref "C6") (pin "2") (pinfunction "2_2") (pintype "passive"))
      (node (ref "C7") (pin "1") (pinfunction "1_1") (pintype "passive"))
      (node (ref "C8") (pin "2") (pinfunction "2_2") (pintype "passive"))
      (node (ref "C9") (pin "1") (pinfunction "1_1") (pintype "passive"))
      (node (ref "CONN1") (pin "1") (pinfunction "GND_1") (pintype "passive"))
      (node (ref "CONN1") (pin "MT1") (pinfunction "MT_MT1") (pintype "bidirectional"))
      (node (ref "CONN1") (pin "MT2") (pinfunction "MT_MT2") (pintype "bidirectional"))
      (node (ref "IC1") (pin "1") (pinfunction "OE_1") (pintype "input"))
      (node (ref "IC1") (pin "3") (pinfunction "GND_3") (pintype "power_in"))
      (node (ref "IC3") (pin "19") (pinfunction "TESTEN_19") (pintype "input"))
      (node (ref "IC3") (pin "P$1") (pinfunction "GND_P$1") (pintype "power_in"))
      (node (ref "L") (pin "C") (pinfunction "C_C") (pintype "passive"))
      (node (ref "LED1") (pin "3-GND") (pinfunction "GND_3-GND") (pintype "power_in"))
      (node (ref "LED10") (pin "3-GND") (pinfunction "GND_3-GND") (pintype "power_in"))
      (node (ref "LED11") (pin "3-GND") (pinfunction "GND_3-GND") (pintype "power_in"))
      (node (ref "LED12") (pin "3-GND") (pinfunction "GND_3-GND") (pintype "power_in"))
      (node (ref "LED2") (pin "3-GND") (pinfunction "GND_3-GND") (pintype "power_in"))
      (node (ref "LED3") (pin "3-GND") (pinfunction "GND_3-GND") (pintype "power_in"))
      (node (ref "LED4") (pin "3-GND") (pinfunction "GND_3-GND") (pintype "power_in"))
      (node (ref "LED5") (pin "3-GND") (pinfunction "GND_3-GND") (pintype "power_in"))
      (node (ref "LED6") (pin "3-GND") (pinfunction "GND_3-GND") (pintype "power_in"))
      (node (ref "LED7") (pin "3-GND") (pinfunction "GND_3-GND") (pintype "power_in"))
      (node (ref "LED8") (pin "3-GND") (pinfunction "GND_3-GND") (pintype "power_in"))
      (node (ref "LED9") (pin "3-GND") (pinfunction "GND_3-GND") (pintype "power_in"))
      (node (ref "R1") (pin "2") (pinfunction "1_2") (pintype "passive"))
      (node (ref "R1") (pin "3") (pinfunction "1_3") (pintype "passive"))
      (node (ref "R12") (pin "1") (pinfunction "1_1") (pintype "passive"))
      (node (ref "R14") (pin "5") (pinfunction "2_5") (pintype "passive"))
      (node (ref "R15") (pin "2") (pinfunction "2_2") (pintype "passive"))
      (node (ref "R17") (pin "1") (pinfunction "1_1") (pintype "passive"))
      (node (ref "R7") (pin "1") (pinfunction "1_1") (pintype "passive"))
      (node (ref "SW2") (pin "1") (pinfunction "P_1") (pintype "passive"))
      (node (ref "SW2") (pin "MT1") (pinfunction "MT_MT1") (pintype "bidirectional"))
      (node (ref "SW2") (pin "MT2") (pinfunction "MT_MT2") (pintype "bidirectional"))
      (node (ref "SW3") (pin "C") (pinfunction "COM_C") (pintype "bidirectional"))
      (node (ref "SW3") (pin "D") (pinfunction "D_D") (pintype "bidirectional"))
      (node (ref "SW3") (pin "P$1") (pinfunction "MECH_P$1") (pintype "bidirectional"))
      (node (ref "SW3") (pin "P$2") (pinfunction "MECH_P$2") (pintype "bidirectional"))
      (node (ref "U$1") (pin "2") (pinfunction "2_2") (pintype "passive"))
      (node (ref "U$12") (pin "2") (pinfunction "2_2") (pintype "passive"))
      (node (ref "U$13") (pin "2") (pinfunction "2_2") (pintype "passive"))
      (node (ref "U$2") (pin "2") (pinfunction "2_2") (pintype "passive"))
      (node (ref "U$3") (pin "2") (pinfunction "2_2") (pintype "passive"))
      (node (ref "U$4") (pin "2") (pinfunction "2_2") (pintype "passive"))
      (node (ref "U$40") (pin "2") (pinfunction "2_2") (pintype "passive"))
      (node (ref "U$41") (pin "2") (pinfunction "2_2") (pintype "passive"))
      (node (ref "U$42") (pin "2") (pinfunction "2_2") (pintype "passive"))
      (node (ref "U$43") (pin "2") (pinfunction "2_2") (pintype "passive"))
      (node (ref "U$5") (pin "2") (pinfunction "2_2") (pintype "passive"))
      (node (ref "U$6") (pin "2") (pinfunction "2_2") (pintype "passive"))
      (node (ref "U1") (pin "4") (pinfunction "VSS_4") (pintype "bidirectional"))
      (node (ref "U1") (pin "PAD") (pinfunction "VSS_PAD") (pintype "bidirectional"))
      (node (ref "U2") (pin "2") (pinfunction "GND_2") (pintype "power_in"))
      (node (ref "U3") (pin "7") (pinfunction "GND_7") (pintype "power_in"))
      (node (ref "X1") (pin "A1B12") (pinfunction "GND_A1B12") (pintype "power_in"))
      (node (ref "X1") (pin "B1A12") (pinfunction "GND_B1A12") (pintype "power_in"))
      (node (ref "X2") (pin "16") (pinfunction "VSS_16") (pintype "power_in"))
      (node (ref "X2") (pin "6") (pinfunction "VSS_6") (pintype "power_in"))
      (node (ref "X2") (pin "SUPPORT1") (pinfunction "VSS_SUPPORT1") (pintype "power_in"))
      (node (ref "X2") (pin "SUPPORT2") (pinfunction "VSS_SUPPORT2") (pintype "power_in"))
    )
    (net (code "9") (name "GP1") (class "Default")
      (node (ref "IC3") (pin "3") (pinfunction "GPIO1_3") (pintype "bidirectional"))
      (node (ref "U$40") (pin "1") (pinfunction "1_1") (pintype "passive"))
    )
    (net (code "10") (name "GP2") (class "Default")
      (node (ref "IC3") (pin "4") (pinfunction "GPIO2_4") (pintype "bidirectional"))
      (node (ref "U$13") (pin "1") (pinfunction "1_1") (pintype "passive"))
    )
    (net (code "11") (name "GP3") (class "Default")
      (node (ref "IC3") (pin "5") (pinfunction "GPIO3_5") (pintype "bidirectional"))
      (node (ref "U$12") (pin "1") (pinfunction "1_1") (pintype "passive"))
    )
    (net (code "12") (name "GP4") (class "Default")
      (node (ref "IC3") (pin "6") (pinfunction "GPIO4_6") (pintype "bidirectional"))
      (node (ref "U$43") (pin "1") (pinfunction "1_1") (pintype "passive"))
    )
    (net (code "13") (name "GP5") (class "Default")
      (node (ref "IC3") (pin "7") (pinfunction "GPIO5_7") (pintype "bidirectional"))
      (node (ref "U$42") (pin "1") (pinfunction "1_1") (pintype "passive"))
    )
    (net (code "14") (name "GP6") (class "Default")
      (node (ref "IC3") (pin "8") (pinfunction "GPIO6_8") (pintype "bidirectional"))
      (node (ref "U$41") (pin "1") (pinfunction "1_1") (pintype "passive"))
    )
    (net (code "15") (name "GP7") (class "Default")
      (node (ref "IC3") (pin "9") (pinfunction "GPIO7_9") (pintype "bidirectional"))
      (node (ref "U$6") (pin "1") (pinfunction "1_1") (pintype "passive"))
    )
    (net (code "16") (name "GP8") (class "Default")
      (node (ref "IC3") (pin "11") (pinfunction "GPIO8_11") (pintype "bidirectional"))
      (node (ref "U$5") (pin "1") (pinfunction "1_1") (pintype "passive"))
    )
    (net (code "17") (name "GP9") (class "Default")
      (node (ref "IC3") (pin "12") (pinfunction "GPIO9_12") (pintype "bidirectional"))
      (node (ref "U$4") (pin "1") (pinfunction "1_1") (pintype "passive"))
    )
    (net (code "18") (name "GP10") (class "Default")
      (node (ref "IC3") (pin "13") (pinfunction "GPIO10_13") (pintype "bidirectional"))
      (node (ref "U$1") (pin "1") (pinfunction "1_1") (pintype "passive"))
    )
    (net (code "19") (name "GP11") (class "Default")
      (node (ref "IC3") (pin "14") (pinfunction "GPIO11_14") (pintype "bidirectional"))
      (node (ref "U$2") (pin "1") (pinfunction "1_1") (pintype "passive"))
    )
    (net (code "20") (name "GP12") (class "Default")
      (node (ref "IC3") (pin "15") (pinfunction "GPIO12_15") (pintype "bidirectional"))
      (node (ref "U$3") (pin "1") (pinfunction "1_1") (pintype "passive"))
    )
    (net (code "21") (name "LED") (class "Default")
      (node (ref "IC3") (pin "16") (pinfunction "GPIO13_16") (pintype "bidirectional"))
      (node (ref "R1") (pin "1") (pinfunction "1_1") (pintype "passive"))
    )
    (net (code "22") (name "MISO") (class "Default")
      (node (ref "IC3") (pin "40") (pinfunction "GPIO28/AD2_40") (pintype "bidirectional"))
    )
    (net (code "23") (name "MOSI") (class "Default")
      (node (ref "IC3") (pin "39") (pinfunction "GPIO27/AD1_39") (pintype "bidirectional"))
      (node (ref "X2") (pin "12") (pinfunction "MOSI_12") (pintype "input"))
    )
    (net (code "24") (name "NEOPIX") (class "Default")
      (node (ref "IC1") (pin "2") (pinfunction "I_2") (pintype "input"))
      (node (ref "IC3") (pin "30") (pinfunction "GPIO19_30") (pintype "bidirectional"))
      (node (ref "R7") (pin "2") (pinfunction "2_2") (pintype "passive"))
    )
    (net (code "25") (name "NEOPIX_5V") (class "Default")
      (node (ref "IC1") (pin "4") (pinfunction "O_4") (pintype "tri_state"))
      (node (ref "LED1") (pin "4-DIN") (pinfunction "DI_4-DIN") (pintype "input"))
    )
    (net (code "26") (name "Net-(C20-Pad2)") (class "Default")
      (node (ref "C20") (pin "2") (pinfunction "2_2") (pintype "passive"))
      (node (ref "R6") (pin "1") (pinfunction "1_1") (pintype "passive"))
      (node (ref "Y1") (pin "1") (pinfunction "1_1") (pintype "passive"))
    )
    (net (code "27") (name "Net-(C32-Pad1)") (class "Default")
      (node (ref "C32") (pin "1") (pinfunction "1_1") (pintype "passive"))
      (node (ref "C33") (pin "2") (pinfunction "2_2") (pintype "passive"))
      (node (ref "R16") (pin "2") (pinfunction "2_2") (pintype "passive"))
      (node (ref "R17") (pin "2") (pinfunction "2_2") (pintype "passive"))
    )
    (net (code "28") (name "Net-(C32-Pad2)") (class "Default")
      (node (ref "C32") (pin "2") (pinfunction "2_2") (pintype "passive"))
      (node (ref "R13") (pin "1") (pinfunction "1_1") (pintype "passive"))
    )
    (net (code "29") (name "Net-(C34-Pad1)") (class "Default")
      (node (ref "C34") (pin "1") (pinfunction "1_1") (pintype "passive"))
      (node (ref "R18") (pin "1") (pinfunction "1_1") (pintype "passive"))
    )
    (net (code "30") (name "Net-(D3-PadA)") (class "Default")
      (node (ref "D3") (pin "A") (pinfunction "A_A") (pintype "passive"))
      (node (ref "R11") (pin "2") (pinfunction "2_2") (pintype "passive"))
    )
    (net (code "31") (name "Net-(IC3-XIN)") (class "Default")
      (node (ref "C19") (pin "2") (pinfunction "2_2") (pintype "passive"))
      (node (ref "IC3") (pin "20") (pinfunction "XIN_20") (pintype "input"))
      (node (ref "Y1") (pin "3") (pinfunction "2_3") (pintype "passive"))
    )
    (net (code "32") (name "Net-(IC3-XOUT)") (class "Default")
      (node (ref "IC3") (pin "21") (pinfunction "XOUT_21") (pintype "output"))
      (node (ref "R6") (pin "2") (pinfunction "2_2") (pintype "passive"))
    )
    (net (code "33") (name "Net-(LED1-DO)") (class "Default")
      (node (ref "LED1") (pin "2-DOUT") (pinfunction "DO_2-DOUT") (pintype "output"))
      (node (ref "LED2") (pin "4-DIN") (pinfunction "DI_4-DIN") (pintype "input"))
    )
    (net (code "34") (name "Net-(LED2-DO)") (class "Default")
      (node (ref "LED2") (pin "2-DOUT") (pinfunction "DO_2-DOUT") (pintype "output"))
      (node (ref "LED3") (pin "4-DIN") (pinfunction "DI_4-DIN") (pintype "input"))
    )
    (net (code "35") (name "Net-(LED3-DO)") (class "Default")
      (node (ref "LED3") (pin "2-DOUT") (pinfunction "DO_2-DOUT") (pintype "output"))
      (node (ref "LED4") (pin "4-DIN") (pinfunction "DI_4-DIN") (pintype "input"))
    )
    (net (code "36") (name "Net-(LED4-DO)") (class "Default")
      (node (ref "LED4") (pin "2-DOUT") (pinfunction "DO_2-DOUT") (pintype "output"))
      (node (ref "LED5") (pin "4-DIN") (pinfunction "DI_4-DIN") (pintype "input"))
    )
    (net (code "37") (name "Net-(LED5-DO)") (class "Default")
      (node (ref "LED5") (pin "2-DOUT") (pinfunction "DO_2-DOUT") (pintype "output"))
      (node (ref "LED6") (pin "4-DIN") (pinfunction "DI_4-DIN") (pintype "input"))
    )
    (net (code "38") (name "Net-(LED6-DO)") (class "Default")
      (node (ref "LED6") (pin "2-DOUT") (pinfunction "DO_2-DOUT") (pintype "output"))
      (node (ref "LED7") (pin "4-DIN") (pinfunction "DI_4-DIN") (pintype "input"))
    )
    (net (code "39") (name "Net-(LED7-DO)") (class "Default")
      (node (ref "LED7") (pin "2-DOUT") (pinfunction "DO_2-DOUT") (pintype "output"))
      (node (ref "LED8") (pin "4-DIN") (pinfunction "DI_4-DIN") (pintype "input"))
    )
    (net (code "40") (name "Net-(LED8-DO)") (class "Default")
      (node (ref "LED8") (pin "2-DOUT") (pinfunction "DO_2-DOUT") (pintype "output"))
      (node (ref "LED9") (pin "4-DIN") (pinfunction "DI_4-DIN") (pintype "input"))
    )
    (net (code "41") (name "Net-(LED10-DI)") (class "Default")
      (node (ref "LED10") (pin "4-DIN") (pinfunction "DI_4-DIN") (pintype "input"))
      (node (ref "LED9") (pin "2-DOUT") (pinfunction "DO_2-DOUT") (pintype "output"))
    )
    (net (code "42") (name "Net-(LED10-DO)") (class "Default")
      (node (ref "LED10") (pin "2-DOUT") (pinfunction "DO_2-DOUT") (pintype "output"))
      (node (ref "LED11") (pin "4-DIN") (pinfunction "DI_4-DIN") (pintype "input"))
    )
    (net (code "43") (name "Net-(LED11-DO)") (class "Default")
      (node (ref "LED11") (pin "2-DOUT") (pinfunction "DO_2-DOUT") (pintype "output"))
      (node (ref "LED12") (pin "4-DIN") (pinfunction "DI_4-DIN") (pintype "input"))
    )
    (net (code "44") (name "Net-(R1A-2)") (class "Default")
      (node (ref "L") (pin "A") (pinfunction "A_A") (pintype "passive"))
      (node (ref "R1") (pin "8") (pinfunction "2_8") (pintype "passive"))
    )
    (net (code "45") (name "Net-(R3-Pad1)") (class "Default")
      (node (ref "R3") (pin "1") (pinfunction "1_1") (pintype "passive"))
      (node (ref "X1") (pin "A6") (pinfunction "D+_A6") (pintype "bidirectional"))
      (node (ref "X1") (pin "B6") (pinfunction "D+_B6") (pintype "bidirectional"))
    )
    (net (code "46") (name "Net-(R4-Pad1)") (class "Default")
      (node (ref "R4") (pin "1") (pinfunction "1_1") (pintype "passive"))
      (node (ref "X1") (pin "A7") (pinfunction "D-_A7") (pintype "bidirectional"))
      (node (ref "X1") (pin "B7") (pinfunction "D-_B7") (pintype "bidirectional"))
    )
    (net (code "47") (name "Net-(U3-IN_N)") (class "Default")
      (node (ref "R18") (pin "2") (pinfunction "2_2") (pintype "passive"))
      (node (ref "U3") (pin "4") (pinfunction "IN_N_4") (pintype "input"))
    )
    (net (code "48") (name "Net-(U3-IN_P)") (class "Default")
      (node (ref "R13") (pin "2") (pinfunction "2_2") (pintype "passive"))
      (node (ref "U3") (pin "3") (pinfunction "IN_P_3") (pintype "input"))
    )
    (net (code "49") (name "Net-(U3-VO_N)") (class "Default")
      (node (ref "SP1") (pin "+") (pinfunction "+_+") (pintype "passive"))
      (node (ref "U3") (pin "8") (pinfunction "VO_N_8") (pintype "output"))
    )
    (net (code "50") (name "Net-(U3-VO_P)") (class "Default")
      (node (ref "SP1") (pin "-") (pinfunction "-_-") (pintype "passive"))
      (node (ref "U3") (pin "5") (pinfunction "VO_P_5") (pintype "output"))
    )
    (net (code "51") (name "Net-(X2-C1+)") (class "Default")
      (node (ref "C15") (pin "2") (pinfunction "2_2") (pintype "passive"))
      (node (ref "X2") (pin "3") (pinfunction "C1+_3") (pintype "input"))
    )
    (net (code "52") (name "Net-(X2-C1-)") (class "Default")
      (node (ref "C15") (pin "1") (pinfunction "1_1") (pintype "passive"))
      (node (ref "X2") (pin "4") (pinfunction "C1-_4") (pintype "input"))
    )
    (net (code "53") (name "Net-(X2-C2+)") (class "Default")
      (node (ref "C17") (pin "2") (pinfunction "2_2") (pintype "passive"))
      (node (ref "X2") (pin "1") (pinfunction "C2+_1") (pintype "input"))
    )
    (net (code "54") (name "Net-(X2-C2-)") (class "Default")
      (node (ref "C17") (pin "1") (pinfunction "1_1") (pintype "passive"))
      (node (ref "X2") (pin "2") (pinfunction "C2-_2") (pintype "input"))
    )
    (net (code "55") (name "Net-(X2-IREF)") (class "Default")
      (node (ref "R12") (pin "2") (pinfunction "2_2") (pintype "passive"))
      (node (ref "X2") (pin "13") (pinfunction "IREF_13") (pintype "bidirectional"))
    )
    (net (code "56") (name "OLED_CS") (class "Default")
      (node (ref "IC3") (pin "34") (pinfunction "GPIO22_34") (pintype "bidirectional"))
      (node (ref "X2") (pin "8") (pinfunction "~{CS}_8") (pintype "input"))
    )
    (net (code "57") (name "OLED_DC") (class "Default")
      (node (ref "IC3") (pin "36") (pinfunction "GPIO24_36") (pintype "bidirectional"))
      (node (ref "X2") (pin "10") (pinfunction "D/~{C}_10") (pintype "input"))
    )
    (net (code "58") (name "OLED_RST") (class "Default")
      (node (ref "IC3") (pin "35") (pinfunction "GPIO23_35") (pintype "bidirectional"))
      (node (ref "R14") (pin "4") (pinfunction "1_4") (pintype "passive"))
      (node (ref "X2") (pin "9") (pinfunction "~{RES}_9") (pintype "input"))
    )
    (net (code "59") (name "QSPI_CS") (class "Default")
      (node (ref "IC3") (pin "56") (pinfunction "~{QSPI_CS}_56") (pintype "bidirectional"))
      (node (ref "R11") (pin "1") (pinfunction "1_1") (pintype "passive"))
      (node (ref "R2") (pin "2") (pinfunction "2_2") (pintype "passive"))
      (node (ref "TP6") (pin "P$1") (pinfunction "P$1_P$1") (pintype "bidirectional"))
      (node (ref "U1") (pin "1") (pinfunction "SSEL_1") (pintype "bidirectional"))
    )
    (net (code "60") (name "QSPI_DATA[0]") (class "Default")
      (node (ref "IC3") (pin "53") (pinfunction "QSPI_SD0_53") (pintype "bidirectional"))
      (node (ref "U1") (pin "5") (pinfunction "MOSI_5") (pintype "bidirectional"))
    )
    (net (code "61") (name "QSPI_DATA[1]") (class "Default")
      (node (ref "IC3") (pin "55") (pinfunction "QSPI_SD1_55") (pintype "bidirectional"))
      (node (ref "U1") (pin "2") (pinfunction "MISO_2") (pintype "bidirectional"))
    )
    (net (code "62") (name "QSPI_DATA[2]") (class "Default")
      (node (ref "IC3") (pin "54") (pinfunction "QSPI_SD2_54") (pintype "bidirectional"))
      (node (ref "U1") (pin "3") (pinfunction "WP#/IO2_3") (pintype "bidirectional"))
    )
    (net (code "63") (name "QSPI_DATA[3]") (class "Default")
      (node (ref "IC3") (pin "51") (pinfunction "QSPI_SD3_51") (pintype "bidirectional"))
      (node (ref "U1") (pin "7") (pinfunction "HOLD#/IO3_7") (pintype "bidirectional"))
    )
    (net (code "64") (name "QSPI_SCK") (class "Default")
      (node (ref "IC3") (pin "52") (pinfunction "QSPI_SCLK_52") (pintype "bidirectional"))
      (node (ref "U1") (pin "6") (pinfunction "SCK_6") (pintype "bidirectional"))
    )
    (net (code "65") (name "ROTA") (class "Default")
      (node (ref "IC3") (pin "28") (pinfunction "GPIO17_28") (pintype "bidirectional"))
      (node (ref "SW3") (pin "A") (pinfunction "A_A") (pintype "bidirectional"))
    )
    (net (code "66") (name "ROTB") (class "Default")
      (node (ref "IC3") (pin "29") (pinfunction "GPIO18_29") (pintype "bidirectional"))
      (node (ref "SW3") (pin "B") (pinfunction "B_B") (pintype "bidirectional"))
    )
    (net (code "67") (name "SCK") (class "Default")
      (node (ref "IC3") (pin "38") (pinfunction "GPIO26/AD0_38") (pintype "bidirectional"))
      (node (ref "X2") (pin "11") (pinfunction "SCK_11") (pintype "input"))
    )
    (net (code "68") (name "SCL") (class "Default")
      (node (ref "CONN1") (pin "4") (pinfunction "SCL_4") (pintype "passive"))
      (node (ref "IC3") (pin "32") (pinfunction "GPIO21_32") (pintype "bidirectional"))
      (node (ref "R14") (pin "3") (pinfunction "1_3") (pintype "passive"))
    )
    (net (code "69") (name "SDA") (class "Default")
      (node (ref "CONN1") (pin "3") (pinfunction "SDA_3") (pintype "passive"))
      (node (ref "IC3") (pin "31") (pinfunction "GPIO20_31") (pintype "bidirectional"))
      (node (ref "R14") (pin "2") (pinfunction "1_2") (pintype "passive"))
    )
    (net (code "70") (name "SPEAKER") (class "Default")
      (node (ref "IC3") (pin "27") (pinfunction "GPIO16_27") (pintype "bidirectional"))
      (node (ref "R16") (pin "1") (pinfunction "1_1") (pintype "passive"))
    )
    (net (code "71") (name "SPKR_SD") (class "Default")
      (node (ref "IC3") (pin "17") (pinfunction "GPIO14_17") (pintype "bidirectional"))
      (node (ref "R15") (pin "1") (pinfunction "1_1") (pintype "passive"))
      (node (ref "U3") (pin "1") (pinfunction "/SD_1") (pintype "input"))
    )
    (net (code "72") (name "USBBOOT") (class "Default")
      (node (ref "D3") (pin "C") (pinfunction "C_C") (pintype "passive"))
      (node (ref "IC3") (pin "2") (pinfunction "GPIO0_2") (pintype "bidirectional"))
      (node (ref "SW3") (pin "E") (pinfunction "E_E") (pintype "bidirectional"))
    )
    (net (code "73") (name "VCC") (class "Default")
      (node (ref "C14") (pin "2") (pinfunction "2_2") (pintype "passive"))
      (node (ref "X2") (pin "15") (pinfunction "VCC_15") (pintype "power_in"))
    )
    (net (code "74") (name "VCOMH") (class "Default")
      (node (ref "C9") (pin "2") (pinfunction "2_2") (pintype "passive"))
      (node (ref "X2") (pin "14") (pinfunction "VCOMH_14") (pintype "power_in"))
    )
    (net (code "75") (name "unconnected-(IC3-GPIO15-Pad18)") (class "Default")
      (node (ref "IC3") (pin "18") (pinfunction "GPIO15_18") (pintype "bidirectional"))
    )
    (net (code "76") (name "unconnected-(IC3-GPIO25-Pad37)") (class "Default")
      (node (ref "IC3") (pin "37") (pinfunction "GPIO25_37") (pintype "bidirectional"))
    )
    (net (code "77") (name "unconnected-(IC3-GPIO29{slash}AD3-Pad41)") (class "Default")
      (node (ref "IC3") (pin "41") (pinfunction "GPIO29/AD3_41") (pintype "bidirectional"))
    )
    (net (code "78") (name "unconnected-(IC3-SWCLK-Pad24)") (class "Default")
      (node (ref "IC3") (pin "24") (pinfunction "SWCLK_24") (pintype "bidirectional"))
    )
    (net (code "79") (name "unconnected-(IC3-SWDIO-Pad25)") (class "Default")
      (node (ref "IC3") (pin "25") (pinfunction "SWDIO_25") (pintype "bidirectional"))
    )
    (net (code "80") (name "unconnected-(LED12-DO-Pad2-DOUT)") (class "Default")
      (node (ref "LED12") (pin "2-DOUT") (pinfunction "DO_2-DOUT") (pintype "output"))
    )
    (net (code "81") (name "unconnected-(TP1-SEW-PadP$1)") (class "Default")
      (node (ref "TP1") (pin "P$1") (pinfunction "SEW_P$1") (pintype "bidirectional"))
    )
    (net (code "82") (name "unconnected-(TP2-SEW-PadP$1)") (class "Default")
      (node (ref "TP2") (pin "P$1") (pinfunction "SEW_P$1") (pintype "bidirectional"))
    )
    (net (code "83") (name "unconnected-(TP3-SEW-PadP$1)") (class "Default")
      (node (ref "TP3") (pin "P$1") (pinfunction "SEW_P$1") (pintype "bidirectional"))
    )
    (net (code "84") (name "unconnected-(TP4-SEW-PadP$1)") (class "Default")
      (node (ref "TP4") (pin "P$1") (pinfunction "SEW_P$1") (pintype "bidirectional"))
    )
    (net (code "85") (name "unconnected-(U2-P4-Pad4)") (class "Default")
      (node (ref "U2") (pin "4") (pinfunction "P4_4") (pintype "bidirectional"))
    )
    (net (code "86") (name "unconnected-(U3-NC-Pad2)") (class "Default")
      (node (ref "U3") (pin "2") (pinfunction "NC_2") (pintype "no_connect"))
    )
    (net (code "87") (name "unconnected-(X1-SBU1-PadA8)") (class "Default")
      (node (ref "X1") (pin "A8") (pinfunction "SBU1_A8") (pintype "bidirectional"))
    )
    (net (code "88") (name "unconnected-(X1-SBU2-PadB8)") (class "Default")
      (node (ref "X1") (pin "B8") (pinfunction "SBU2_B8") (pintype "bidirectional"))
    )
    (net (code "89") (name "~{RESET}") (class "Default")
      (node (ref "IC3") (pin "26") (pinfunction "/RUN_26") (pintype "bidirectional"))
      (node (ref "R14") (pin "1") (pinfunction "1_1") (pintype "passive"))
      (node (ref "SW2") (pin "2") (pinfunction "S_2") (pintype "passive"))
      (node (ref "TP5") (pin "P$1") (pinfunction "P$1_P$1") (pintype "bidirectional"))
    )
  )
)
